# XC_Tail_Lights.net
KiCad netlist of a schematic drawn in Altium Designer
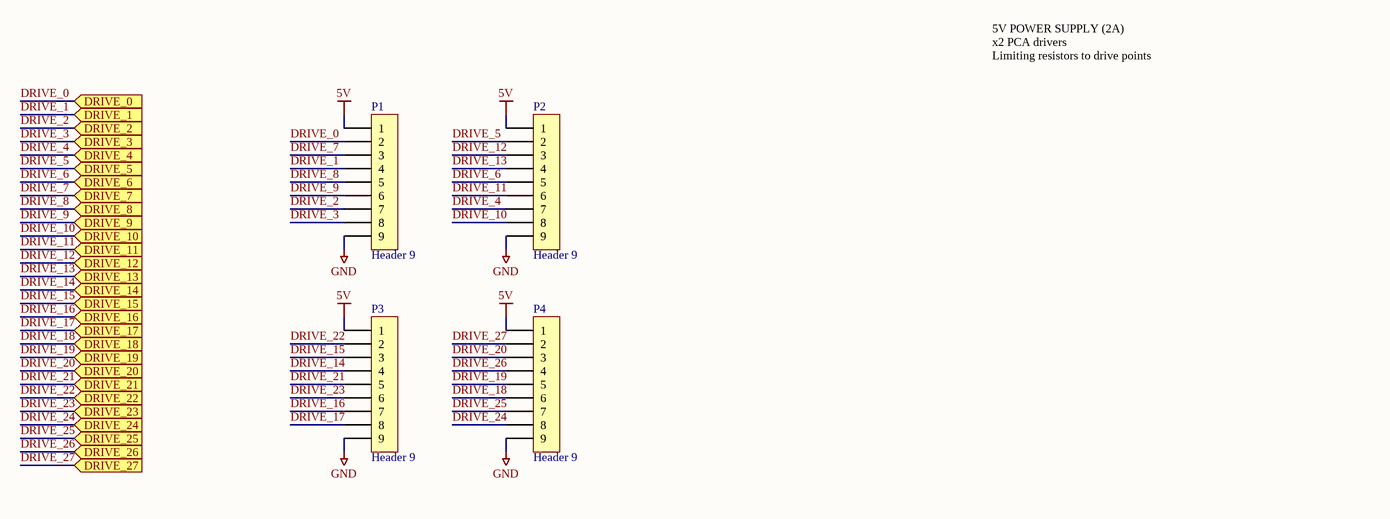
[diagram p0: XC Tail Lights.SchDoc]

(export (version "E")
  (design (tool "Eeschema 10.0.6"))
  (components
    (comp (ref "P1")
      (value "Header 9")
      (footprint "HEADER 1x9")
      (description "Header, 9-Pin")
      (fields (field (name "PUBLISHER") "Altium Limited"))
      (libsource (lib "LED TAIL LIGHTS") (part "Header 9"))
    )
    (comp (ref "P2")
      (value "Header 9")
      (footprint "HEADER 1x9")
      (description "Header, 9-Pin")
      (fields (field (name "PUBLISHER") "Altium Limited"))
      (libsource (lib "LED TAIL LIGHTS") (part "Header 9"))
    )
    (comp (ref "P3")
      (value "Header 9")
      (footprint "HEADER 1x9")
      (description "Header, 9-Pin")
      (fields (field (name "PUBLISHER") "Altium Limited"))
      (libsource (lib "LED TAIL LIGHTS") (part "Header 9"))
    )
    (comp (ref "P4")
      (value "Header 9")
      (footprint "HEADER 1x9")
      (description "Header, 9-Pin")
      (fields (field (name "PUBLISHER") "Altium Limited"))
      (libsource (lib "LED TAIL LIGHTS") (part "Header 9"))
    )
  )
  (nets
    (net (code "1") (name "/DRIVE_0") (class "Default")
      (node (ref "P1") (pin "2") (pinfunction "2_2") (pintype "passive"))
    )
    (net (code "2") (name "/DRIVE_1") (class "Default")
      (node (ref "P1") (pin "4") (pinfunction "4_4") (pintype "passive"))
    )
    (net (code "3") (name "/DRIVE_2") (class "Default")
      (node (ref "P1") (pin "7") (pinfunction "7_7") (pintype "passive"))
    )
    (net (code "4") (name "/DRIVE_3") (class "Default")
      (node (ref "P1") (pin "8") (pinfunction "8_8") (pintype "passive"))
    )
    (net (code "5") (name "/DRIVE_4") (class "Default")
      (node (ref "P2") (pin "7") (pinfunction "7_7") (pintype "passive"))
    )
    (net (code "6") (name "/DRIVE_5") (class "Default")
      (node (ref "P2") (pin "2") (pinfunction "2_2") (pintype "passive"))
    )
    (net (code "7") (name "/DRIVE_6") (class "Default")
      (node (ref "P2") (pin "5") (pinfunction "5_5") (pintype "passive"))
    )
    (net (code "8") (name "/DRIVE_7") (class "Default")
      (node (ref "P1") (pin "3") (pinfunction "3_3") (pintype "passive"))
    )
    (net (code "9") (name "/DRIVE_8") (class "Default")
      (node (ref "P1") (pin "5") (pinfunction "5_5") (pintype "passive"))
    )
    (net (code "10") (name "/DRIVE_9") (class "Default")
      (node (ref "P1") (pin "6") (pinfunction "6_6") (pintype "passive"))
    )
    (net (code "11") (name "/DRIVE_10") (class "Default")
      (node (ref "P2") (pin "8") (pinfunction "8_8") (pintype "passive"))
    )
    (net (code "12") (name "/DRIVE_11") (class "Default")
      (node (ref "P2") (pin "6") (pinfunction "6_6") (pintype "passive"))
    )
    (net (code "13") (name "/DRIVE_12") (class "Default")
      (node (ref "P2") (pin "3") (pinfunction "3_3") (pintype "passive"))
    )
    (net (code "14") (name "/DRIVE_13") (class "Default")
      (node (ref "P2") (pin "4") (pinfunction "4_4") (pintype "passive"))
    )
    (net (code "15") (name "/DRIVE_14") (class "Default")
      (node (ref "P3") (pin "4") (pinfunction "4_4") (pintype "passive"))
    )
    (net (code "16") (name "/DRIVE_15") (class "Default")
      (node (ref "P3") (pin "3") (pinfunction "3_3") (pintype "passive"))
    )
    (net (code "17") (name "/DRIVE_16") (class "Default")
      (node (ref "P3") (pin "7") (pinfunction "7_7") (pintype "passive"))
    )
    (net (code "18") (name "/DRIVE_17") (class "Default")
      (node (ref "P3") (pin "8") (pinfunction "8_8") (pintype "passive"))
    )
    (net (code "19") (name "/DRIVE_18") (class "Default")
      (node (ref "P4") (pin "6") (pinfunction "6_6") (pintype "passive"))
    )
    (net (code "20") (name "/DRIVE_19") (class "Default")
      (node (ref "P4") (pin "5") (pinfunction "5_5") (pintype "passive"))
    )
    (net (code "21") (name "/DRIVE_20") (class "Default")
      (node (ref "P4") (pin "3") (pinfunction "3_3") (pintype "passive"))
    )
    (net (code "22") (name "/DRIVE_21") (class "Default")
      (node (ref "P3") (pin "5") (pinfunction "5_5") (pintype "passive"))
    )
    (net (code "23") (name "/DRIVE_22") (class "Default")
      (node (ref "P3") (pin "2") (pinfunction "2_2") (pintype "passive"))
    )
    (net (code "24") (name "/DRIVE_23") (class "Default")
      (node (ref "P3") (pin "6") (pinfunction "6_6") (pintype "passive"))
    )
    (net (code "25") (name "/DRIVE_24") (class "Default")
      (node (ref "P4") (pin "8") (pinfunction "8_8") (pintype "passive"))
    )
    (net (code "26") (name "/DRIVE_25") (class "Default")
      (node (ref "P4") (pin "7") (pinfunction "7_7") (pintype "passive"))
    )
    (net (code "27") (name "/DRIVE_26") (class "Default")
      (node (ref "P4") (pin "4") (pinfunction "4_4") (pintype "passive"))
    )
    (net (code "28") (name "/DRIVE_27") (class "Default")
      (node (ref "P4") (pin "2") (pinfunction "2_2") (pintype "passive"))
    )
    (net (code "29") (name "5V") (class "Default")
      (node (ref "P1") (pin "1") (pinfunction "1_1") (pintype "passive"))
      (node (ref "P2") (pin "1") (pinfunction "1_1") (pintype "passive"))
      (node (ref "P3") (pin "1") (pinfunction "1_1") (pintype "passive"))
      (node (ref "P4") (pin "1") (pinfunction "1_1") (pintype "passive"))
    )
    (net (code "30") (name "GND") (class "Default")
      (node (ref "P1") (pin "9") (pinfunction "9_9") (pintype "passive"))
      (node (ref "P2") (pin "9") (pinfunction "9_9") (pintype "passive"))
      (node (ref "P3") (pin "9") (pinfunction "9_9") (pintype "passive"))
      (node (ref "P4") (pin "9") (pinfunction "9_9") (pintype "passive"))
    )
  )
)
